# Battery.net
KiCad netlist of a schematic drawn in Altium Designer
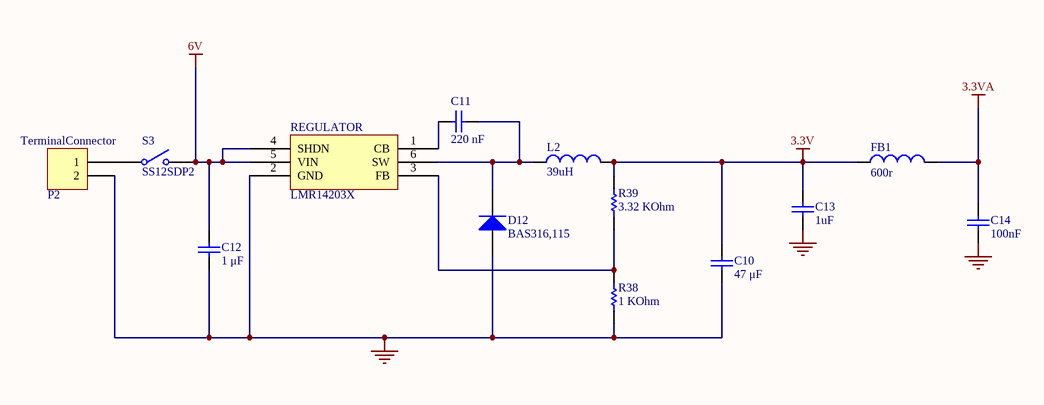
[diagram p0: Battery.SchDoc]

(export (version "E")
  (design (tool "Eeschema 10.0.6"))
  (components
    (comp (ref "C10")
      (value "47 μF")
      (footprint "Capacitor")
      (description "Capacitor")
      (fields (field (name "PUBLISHER") "Altium Limited"))
      (libsource (lib "Miscellaneous Devices") (part "Cap"))
    )
    (comp (ref "C11")
      (value "220 nF")
      (footprint "Capacitor")
      (description "Capacitor")
      (fields (field (name "PUBLISHER") "Altium Limited"))
      (libsource (lib "Miscellaneous Devices") (part "Cap"))
    )
    (comp (ref "C12")
      (value "1 μF")
      (footprint "Capacitor")
      (description "Capacitor")
      (fields (field (name "PUBLISHER") "Altium Limited"))
      (libsource (lib "Miscellaneous Devices") (part "Cap"))
    )
    (comp (ref "C13")
      (value "1uF")
      (footprint "Capacitor")
      (description "Capacitor")
      (fields (field (name "PUBLISHER") "Altium Limited"))
      (libsource (lib "Miscellaneous Devices") (part "Cap"))
    )
    (comp (ref "C14")
      (value "100nF")
      (footprint "Capacitor")
      (description "Capacitor")
      (fields (field (name "PUBLISHER") "Altium Limited"))
      (libsource (lib "Miscellaneous Devices") (part "Cap"))
    )
    (comp (ref "D12")
      (value "BAS316,115")
      (footprint "Didode (Regulator)")
      (description "Default Diode")
      (fields (field (name "PUBLISHER") "Altium Limited"))
      (libsource (lib "Miscellaneous Devices") (part "Diode"))
    )
    (comp (ref "FB1")
      (value "600r")
      (footprint "Inductor")
      (description "Inductor")
      (fields (field (name "Comment") "Comment") (field (name "PUBLISHER") "Altium Limited"))
      (libsource (lib "Miscellaneous Devices") (part "Inductor"))
    )
    (comp (ref "L2")
      (value "39uH")
      (footprint "Inductor (regulator)")
      (description "Inductor")
      (fields (field (name "PUBLISHER") "Altium Limited"))
      (libsource (lib "Miscellaneous Devices") (part "Inductor"))
    )
    (comp (ref "P2")
      (value "TerminalConnector")
      (footprint "TerminalConector")
      (description "Header, 2-Pin, Right Angle")
      (fields (field (name "PUBLISHER") "Altium Limited"))
      (libsource (lib "Miscellaneous Connectors") (part "Header 2H"))
    )
    (comp (ref "R38")
      (value "1 KOhm")
      (footprint "Resistor0603")
      (description "Resistor")
      (fields (field (name "PUBLISHER") "Altium Limited"))
      (libsource (lib "Miscellaneous Devices") (part "Res1"))
    )
    (comp (ref "R39")
      (value "3.32 KOhm")
      (footprint "Resistor0603")
      (description "Resistor")
      (fields (field (name "PUBLISHER") "Altium Limited"))
      (libsource (lib "Miscellaneous Devices") (part "Res1"))
    )
    (comp (ref "REGULATOR")
      (value "LMR14203X")
      (footprint "REGULATOR")
      (libsource (lib "PROBOT_Schema_Library") (part "Regulator"))
    )
    (comp (ref "S3")
      (value "SS12SDP2")
      (footprint "Switch")
      (description "Single-Pole, Single-Throw Switch")
      (fields (field (name "PUBLISHER") "Altium Limited"))
      (libsource (lib "Miscellaneous Devices") (part "SW-SPST"))
    )
  )
  (nets
    (net (code "1") (name "3.3V") (class "Default")
      (node (ref "C10") (pin "2") (pinfunction "2_2") (pintype "passive"))
      (node (ref "C13") (pin "2") (pinfunction "2_2") (pintype "passive"))
      (node (ref "FB1") (pin "1") (pinfunction "1_1") (pintype "passive"))
      (node (ref "L2") (pin "2") (pinfunction "2_2") (pintype "passive"))
      (node (ref "R39") (pin "2") (pinfunction "2_2") (pintype "passive"))
    )
    (net (code "2") (name "3.3VA") (class "Default")
      (node (ref "C14") (pin "2") (pinfunction "2_2") (pintype "passive"))
      (node (ref "FB1") (pin "2") (pinfunction "2_2") (pintype "passive"))
    )
    (net (code "3") (name "6V") (class "Default")
      (node (ref "C12") (pin "2") (pinfunction "2_2") (pintype "passive"))
      (node (ref "REGULATOR") (pin "4") (pinfunction "SHDN_4") (pintype "passive"))
      (node (ref "REGULATOR") (pin "5") (pinfunction "VIN_5") (pintype "passive"))
      (node (ref "S3") (pin "2") (pinfunction "NO_2") (pintype "passive"))
    )
    (net (code "4") (name "GND") (class "Default")
      (node (ref "C10") (pin "1") (pinfunction "1_1") (pintype "passive"))
      (node (ref "C12") (pin "1") (pinfunction "1_1") (pintype "passive"))
      (node (ref "C13") (pin "1") (pinfunction "1_1") (pintype "passive"))
      (node (ref "C14") (pin "1") (pinfunction "1_1") (pintype "passive"))
      (node (ref "D12") (pin "1") (pinfunction "A_1") (pintype "passive"))
      (node (ref "P2") (pin "2") (pinfunction "2_2") (pintype "passive"))
      (node (ref "R38") (pin "1") (pinfunction "1_1") (pintype "passive"))
      (node (ref "REGULATOR") (pin "2") (pinfunction "GND_2") (pintype "passive"))
    )
    (net (code "5") (name "Net-(D12-K)") (class "Default")
      (node (ref "C11") (pin "1") (pinfunction "1_1") (pintype "passive"))
      (node (ref "D12") (pin "2") (pinfunction "K_2") (pintype "passive"))
      (node (ref "L2") (pin "1") (pinfunction "1_1") (pintype "passive"))
      (node (ref "REGULATOR") (pin "6") (pinfunction "SW_6") (pintype "passive"))
    )
    (net (code "6") (name "Net-(REGULATOR-CB)") (class "Default")
      (node (ref "C11") (pin "2") (pinfunction "2_2") (pintype "passive"))
      (node (ref "REGULATOR") (pin "1") (pinfunction "CB_1") (pintype "passive"))
    )
    (net (code "7") (name "Net-(REGULATOR-FB)") (class "Default")
      (node (ref "R38") (pin "2") (pinfunction "2_2") (pintype "passive"))
      (node (ref "R39") (pin "1") (pinfunction "1_1") (pintype "passive"))
      (node (ref "REGULATOR") (pin "3") (pinfunction "FB_3") (pintype "passive"))
    )
    (net (code "8") (name "Net-(S3-COMMON)") (class "Default")
      (node (ref "P2") (pin "1") (pinfunction "1_1") (pintype "passive"))
      (node (ref "S3") (pin "1") (pinfunction "COMMON_1") (pintype "passive"))
    )
  )
)
